# czujniki.net
KiCad netlist of a schematic drawn in EAGLE
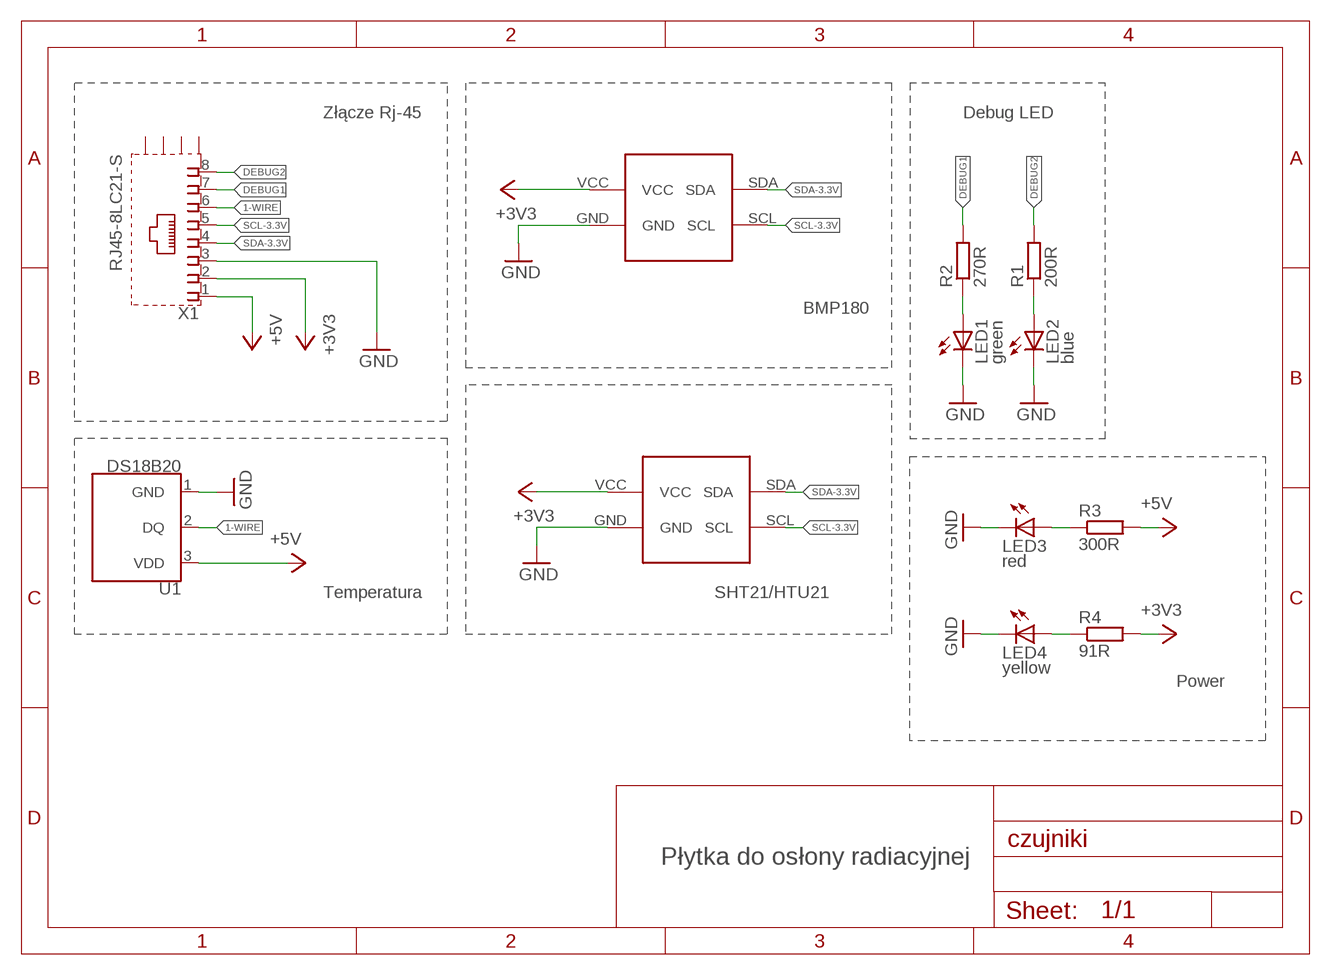
[diagram p0: schematic, sheet 1]

(export (version "E")
  (design (tool "Eeschema 10.0.6"))
  (components
    (comp (ref "LED1")
      (value "green")
      (footprint "eagle-import:CHIPLED_1206")
      (libsource (lib "eagle-import") (part "LEDCHIPLED_1206"))
    )
    (comp (ref "LED2")
      (value "blue")
      (footprint "eagle-import:CHIPLED_1206")
      (libsource (lib "eagle-import") (part "LEDCHIPLED_1206"))
    )
    (comp (ref "LED3")
      (value "red")
      (footprint "eagle-import:CHIPLED_1206")
      (libsource (lib "eagle-import") (part "LEDCHIPLED_1206"))
    )
    (comp (ref "LED4")
      (value "yellow")
      (footprint "eagle-import:CHIPLED_1206")
      (libsource (lib "eagle-import") (part "LEDCHIPLED_1206"))
    )
    (comp (ref "R1")
      (value "200R")
      (footprint "eagle-import:M0805")
      (libsource (lib "eagle-import") (part "R-EU_M0805"))
    )
    (comp (ref "R2")
      (value "270R")
      (footprint "eagle-import:M0805")
      (libsource (lib "eagle-import") (part "R-EU_M0805"))
    )
    (comp (ref "R3")
      (value "300R")
      (footprint "eagle-import:M0805")
      (libsource (lib "eagle-import") (part "R-EU_M0805"))
    )
    (comp (ref "R4")
      (value "91R")
      (footprint "eagle-import:M0805")
      (libsource (lib "eagle-import") (part "R-EU_M0805"))
    )
    (comp (ref "U$1")
      (value "BMP180")
      (footprint "eagle-import:BMP180")
      (libsource (lib "eagle-import") (part "BMP180"))
    )
    (comp (ref "U$2")
      (value "I2C_BOARD")
      (footprint "eagle-import:I2C_BOARD")
      (libsource (lib "eagle-import") (part "I2C_BOARD"))
    )
    (comp (ref "U1")
      (value "DS18B20")
      (footprint "eagle-import:TO-92-AMMO")
      (libsource (lib "eagle-import") (part "DS18B20"))
    )
    (comp (ref "X1")
      (value "RJ45-8LC21-S")
      (footprint "eagle-import:RJ45-SHIELD1")
      (libsource (lib "eagle-import") (part "RJ4521-S-8LC"))
    )
  )
  (nets
    (net (code "1") (name "+3V3") (class "Default")
      (node (ref "R4") (pin "2") (pinfunction "2_2") (pintype "passive"))
      (node (ref "U$1") (pin "VCC") (pinfunction "VCC_VCC") (pintype "bidirectional"))
      (node (ref "U$2") (pin "VCC") (pinfunction "VCC_VCC") (pintype "bidirectional"))
      (node (ref "X1") (pin "2") (pinfunction "2_2") (pintype "passive"))
    )
    (net (code "2") (name "+5V") (class "Default")
      (node (ref "R3") (pin "2") (pinfunction "2_2") (pintype "passive"))
      (node (ref "U1") (pin "3") (pinfunction "VDD_3") (pintype "power_in"))
      (node (ref "X1") (pin "1") (pinfunction "1_1") (pintype "passive"))
    )
    (net (code "3") (name "1-WIRE") (class "Default")
      (node (ref "U1") (pin "2") (pinfunction "DQ_2") (pintype "bidirectional"))
      (node (ref "X1") (pin "6") (pinfunction "6_6") (pintype "passive"))
    )
    (net (code "4") (name "DEBUG1") (class "Default")
      (node (ref "R2") (pin "2") (pinfunction "2_2") (pintype "passive"))
      (node (ref "X1") (pin "7") (pinfunction "7_7") (pintype "passive"))
    )
    (net (code "5") (name "DEBUG2") (class "Default")
      (node (ref "R1") (pin "2") (pinfunction "2_2") (pintype "passive"))
      (node (ref "X1") (pin "8") (pinfunction "8_8") (pintype "passive"))
    )
    (net (code "6") (name "GND") (class "Default")
      (node (ref "LED1") (pin "C") (pinfunction "C_C") (pintype "passive"))
      (node (ref "LED2") (pin "C") (pinfunction "C_C") (pintype "passive"))
      (node (ref "LED3") (pin "C") (pinfunction "C_C") (pintype "passive"))
      (node (ref "LED4") (pin "C") (pinfunction "C_C") (pintype "passive"))
      (node (ref "U$1") (pin "GND") (pinfunction "GND_GND") (pintype "bidirectional"))
      (node (ref "U$2") (pin "GND") (pinfunction "GND_GND") (pintype "bidirectional"))
      (node (ref "U1") (pin "1") (pinfunction "GND_1") (pintype "power_in"))
      (node (ref "X1") (pin "3") (pinfunction "3_3") (pintype "passive"))
    )
    (net (code "7") (name "Net-(LED1-PadA)") (class "Default")
      (node (ref "LED1") (pin "A") (pinfunction "A_A") (pintype "passive"))
      (node (ref "R2") (pin "1") (pinfunction "1_1") (pintype "passive"))
    )
    (net (code "8") (name "Net-(LED2-PadA)") (class "Default")
      (node (ref "LED2") (pin "A") (pinfunction "A_A") (pintype "passive"))
      (node (ref "R1") (pin "1") (pinfunction "1_1") (pintype "passive"))
    )
    (net (code "9") (name "Net-(LED3-PadA)") (class "Default")
      (node (ref "LED3") (pin "A") (pinfunction "A_A") (pintype "passive"))
      (node (ref "R3") (pin "1") (pinfunction "1_1") (pintype "passive"))
    )
    (net (code "10") (name "Net-(LED4-PadA)") (class "Default")
      (node (ref "LED4") (pin "A") (pinfunction "A_A") (pintype "passive"))
      (node (ref "R4") (pin "1") (pinfunction "1_1") (pintype "passive"))
    )
    (net (code "11") (name "SCL-3.3V") (class "Default")
      (node (ref "U$1") (pin "SCL") (pinfunction "SCL_SCL") (pintype "bidirectional"))
      (node (ref "U$2") (pin "SCL") (pinfunction "SCL_SCL") (pintype "bidirectional"))
      (node (ref "X1") (pin "5") (pinfunction "5_5") (pintype "passive"))
    )
    (net (code "12") (name "SDA-3.3V") (class "Default")
      (node (ref "U$1") (pin "SDA") (pinfunction "SDA_SDA") (pintype "bidirectional"))
      (node (ref "U$2") (pin "SDA") (pinfunction "SDA_SDA") (pintype "bidirectional"))
      (node (ref "X1") (pin "4") (pinfunction "4_4") (pintype "passive"))
    )
    (net (code "13") (name "unconnected-(X1-S-PadS1)") (class "Default")
      (node (ref "X1") (pin "S1") (pinfunction "S_S1") (pintype "passive"))
    )
    (net (code "14") (name "unconnected-(X1-S-PadS2)") (class "Default")
      (node (ref "X1") (pin "S2") (pinfunction "S_S2") (pintype "passive"))
    )
    (net (code "15") (name "unconnected-(X1-S-PadS3)") (class "Default")
      (node (ref "X1") (pin "S3") (pinfunction "S_S3") (pintype "passive"))
    )
    (net (code "16") (name "unconnected-(X1-S-PadS4)") (class "Default")
      (node (ref "X1") (pin "S4") (pinfunction "S_S4") (pintype "passive"))
    )
  )
)
